# TA_v2_ESP.net
KiCad netlist of a schematic drawn in EAGLE
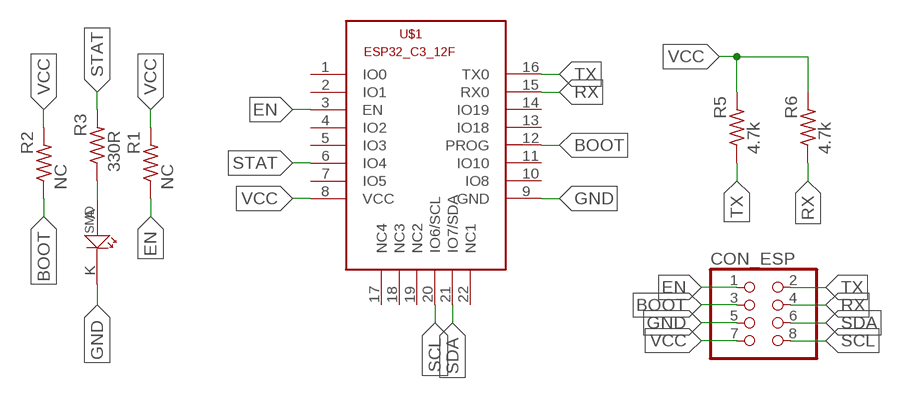
[diagram p0: schematic, sheet 1]

(export (version "E")
  (design (tool "Eeschema 10.0.6"))
  (components
    (comp (ref "CON_ESP")
      (value "PINHD-2X4")
      (footprint "eagle-import:2X04")
      (libsource (lib "eagle-import") (part "PINHD-2X4"))
    )
    (comp (ref "R1")
      (value "NC")
      (footprint "eagle-import:R0603")
      (libsource (lib "eagle-import") (part "R-US_R0603"))
    )
    (comp (ref "R2")
      (value "NC")
      (footprint "eagle-import:R0603")
      (libsource (lib "eagle-import") (part "R-US_R0603"))
    )
    (comp (ref "R3")
      (value "330R")
      (footprint "eagle-import:R0603")
      (libsource (lib "eagle-import") (part "R-US_R0603"))
    )
    (comp (ref "R5")
      (value "4.7k")
      (footprint "eagle-import:R0603")
      (libsource (lib "eagle-import") (part "R-US_R0603"))
    )
    (comp (ref "R6")
      (value "4.7k")
      (footprint "eagle-import:R0603")
      (libsource (lib "eagle-import") (part "R-US_R0603"))
    )
    (comp (ref "U$1")
      (value "ESP32-C3-12FESP32-C3-12F")
      (footprint "eagle-import:ESP32-C3-12F")
      (libsource (lib "eagle-import") (part "ESP32-C3-12FESP32-C3-12F"))
    )
    (comp (ref "U$3")
      (value "LED_SMD")
      (footprint "eagle-import:LED_0603")
      (libsource (lib "eagle-import") (part "LED_SMD"))
    )
  )
  (nets
    (net (code "1") (name "BOOT") (class "Default")
      (node (ref "CON_ESP") (pin "3") (pinfunction "3_3") (pintype "passive"))
      (node (ref "R2") (pin "1") (pinfunction "1_1") (pintype "passive"))
      (node (ref "U$1") (pin "12") (pinfunction "PROG_12") (pintype "bidirectional"))
    )
    (net (code "2") (name "EN") (class "Default")
      (node (ref "CON_ESP") (pin "1") (pinfunction "1_1") (pintype "passive"))
      (node (ref "R1") (pin "1") (pinfunction "1_1") (pintype "passive"))
      (node (ref "U$1") (pin "3") (pinfunction "EN_3") (pintype "bidirectional"))
    )
    (net (code "3") (name "GND") (class "Default")
      (node (ref "CON_ESP") (pin "5") (pinfunction "5_5") (pintype "passive"))
      (node (ref "U$1") (pin "9") (pinfunction "GND_9") (pintype "bidirectional"))
      (node (ref "U$3") (pin "K") (pinfunction "K_K") (pintype "bidirectional"))
    )
    (net (code "4") (name "Net-(R3-Pad1)") (class "Default")
      (node (ref "R3") (pin "1") (pinfunction "1_1") (pintype "passive"))
      (node (ref "U$3") (pin "A") (pinfunction "A_A") (pintype "bidirectional"))
    )
    (net (code "5") (name "RX") (class "Default")
      (node (ref "CON_ESP") (pin "4") (pinfunction "4_4") (pintype "passive"))
      (node (ref "R6") (pin "1") (pinfunction "1_1") (pintype "passive"))
      (node (ref "U$1") (pin "15") (pinfunction "RX0_15") (pintype "bidirectional"))
    )
    (net (code "6") (name "SCL") (class "Default")
      (node (ref "CON_ESP") (pin "8") (pinfunction "8_8") (pintype "passive"))
      (node (ref "U$1") (pin "20") (pinfunction "IO6/SCL_20") (pintype "bidirectional"))
    )
    (net (code "7") (name "SDA") (class "Default")
      (node (ref "CON_ESP") (pin "6") (pinfunction "6_6") (pintype "passive"))
      (node (ref "U$1") (pin "21") (pinfunction "IO7/SDA_21") (pintype "bidirectional"))
    )
    (net (code "8") (name "STAT") (class "Default")
      (node (ref "R3") (pin "2") (pinfunction "2_2") (pintype "passive"))
      (node (ref "U$1") (pin "6") (pinfunction "IO4_6") (pintype "bidirectional"))
    )
    (net (code "9") (name "TX") (class "Default")
      (node (ref "CON_ESP") (pin "2") (pinfunction "2_2") (pintype "passive"))
      (node (ref "R5") (pin "1") (pinfunction "1_1") (pintype "passive"))
      (node (ref "U$1") (pin "16") (pinfunction "TX0_16") (pintype "bidirectional"))
    )
    (net (code "10") (name "VCC") (class "Default")
      (node (ref "CON_ESP") (pin "7") (pinfunction "7_7") (pintype "passive"))
      (node (ref "R1") (pin "2") (pinfunction "2_2") (pintype "passive"))
      (node (ref "R2") (pin "2") (pinfunction "2_2") (pintype "passive"))
      (node (ref "R5") (pin "2") (pinfunction "2_2") (pintype "passive"))
      (node (ref "R6") (pin "2") (pinfunction "2_2") (pintype "passive"))
      (node (ref "U$1") (pin "8") (pinfunction "VCC_8") (pintype "bidirectional"))
    )
    (net (code "11") (name "unconnected-(U$1-IO0-Pad1)") (class "Default")
      (node (ref "U$1") (pin "1") (pinfunction "IO0_1") (pintype "bidirectional"))
    )
    (net (code "12") (name "unconnected-(U$1-IO1-Pad2)") (class "Default")
      (node (ref "U$1") (pin "2") (pinfunction "IO1_2") (pintype "bidirectional"))
    )
    (net (code "13") (name "unconnected-(U$1-IO2-Pad4)") (class "Default")
      (node (ref "U$1") (pin "4") (pinfunction "IO2_4") (pintype "bidirectional"))
    )
    (net (code "14") (name "unconnected-(U$1-IO3-Pad5)") (class "Default")
      (node (ref "U$1") (pin "5") (pinfunction "IO3_5") (pintype "bidirectional"))
    )
    (net (code "15") (name "unconnected-(U$1-IO5-Pad7)") (class "Default")
      (node (ref "U$1") (pin "7") (pinfunction "IO5_7") (pintype "bidirectional"))
    )
    (net (code "16") (name "unconnected-(U$1-IO8-Pad10)") (class "Default")
      (node (ref "U$1") (pin "10") (pinfunction "IO8_10") (pintype "bidirectional"))
    )
    (net (code "17") (name "unconnected-(U$1-IO10-Pad11)") (class "Default")
      (node (ref "U$1") (pin "11") (pinfunction "IO10_11") (pintype "bidirectional"))
    )
    (net (code "18") (name "unconnected-(U$1-IO18-Pad13)") (class "Default")
      (node (ref "U$1") (pin "13") (pinfunction "IO18_13") (pintype "bidirectional"))
    )
    (net (code "19") (name "unconnected-(U$1-IO19-Pad14)") (class "Default")
      (node (ref "U$1") (pin "14") (pinfunction "IO19_14") (pintype "bidirectional"))
    )
    (net (code "20") (name "unconnected-(U$1-NC1-Pad22)") (class "Default")
      (node (ref "U$1") (pin "22") (pinfunction "NC1_22") (pintype "bidirectional"))
    )
    (net (code "21") (name "unconnected-(U$1-NC2-Pad19)") (class "Default")
      (node (ref "U$1") (pin "19") (pinfunction "NC2_19") (pintype "bidirectional"))
    )
    (net (code "22") (name "unconnected-(U$1-NC3-Pad18)") (class "Default")
      (node (ref "U$1") (pin "18") (pinfunction "NC3_18") (pintype "bidirectional"))
    )
    (net (code "23") (name "unconnected-(U$1-NC4-Pad17)") (class "Default")
      (node (ref "U$1") (pin "17") (pinfunction "NC4_17") (pintype "bidirectional"))
    )
  )
)
